# Microprocessor_and_CAN.net
KiCad netlist of a schematic drawn in Altium Designer
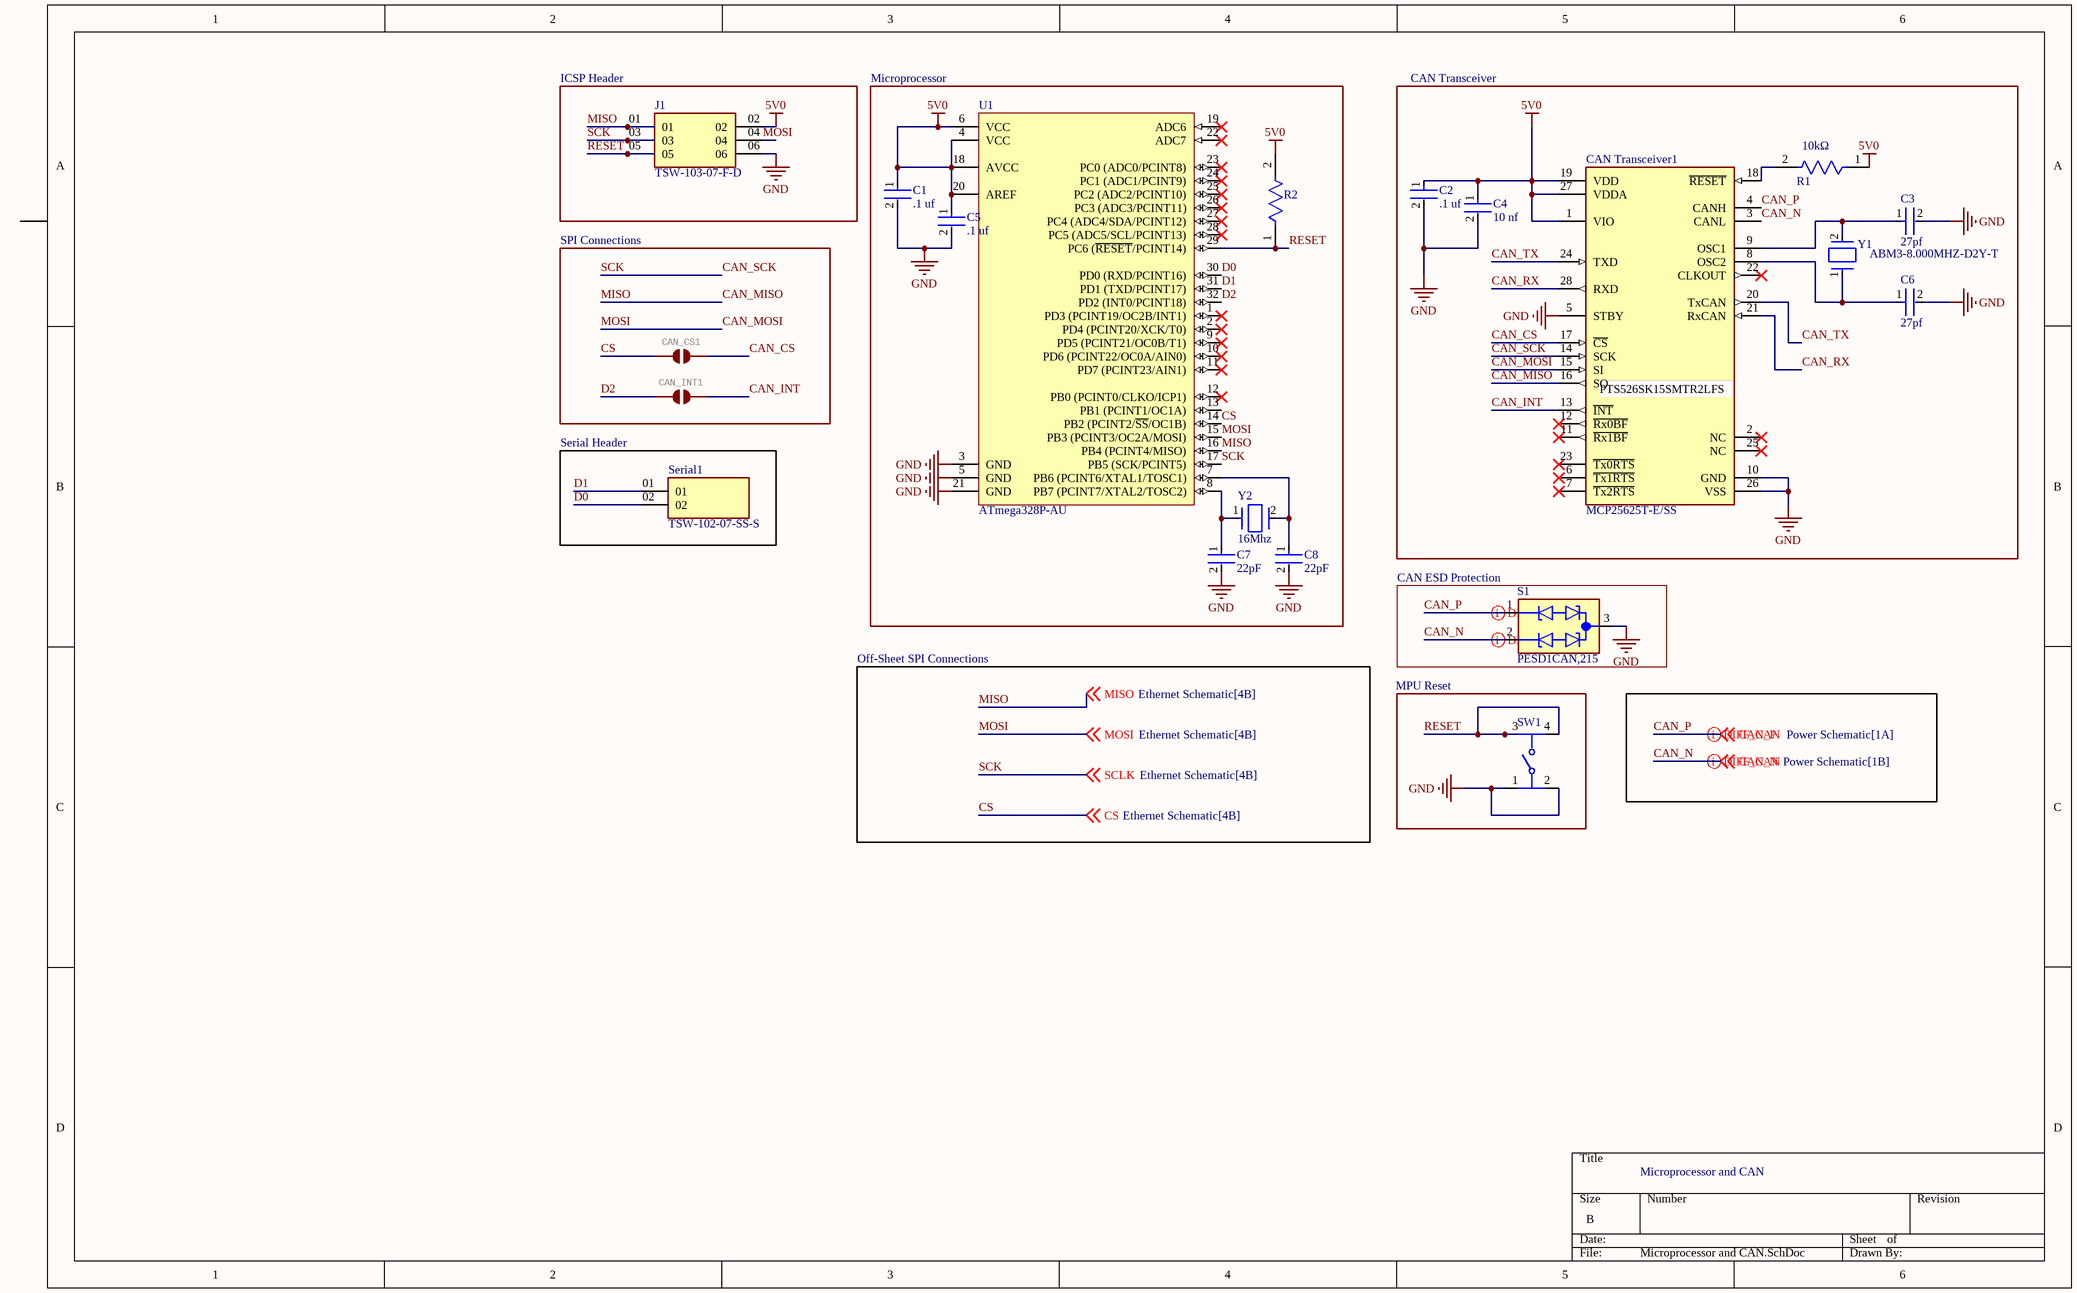
[diagram p0: Microprocessor and CAN.SchDoc]

(export (version "E")
  (design (tool "Eeschema 10.0.6"))
  (components
    (comp (ref "C1")
      (value ".1 uf")
      (footprint "FP-0805-L_2_01_0_2-W_1_25-IPC_B")
      (description "General Purpose Ceramic Capacitor, 0805, 100nF, 10%, X7R, 15%, 100V")
      (fields (field (name "VOLTAGE") "100V") (field (name "TOLERANCE") "10%"))
      (libsource (lib "Altium Content Vault") (part "b4654b650e69147ec39a6b967a45e02"))
    )
    (comp (ref "C2")
      (value ".1 uf")
      (footprint "FP-0805-L_2_01_0_2-W_1_25-IPC_B")
      (description "General Purpose Ceramic Capacitor, 0805, 100nF, 10%, X7R, 15%, 100V")
      (fields (field (name "VOLTAGE") "100V") (field (name "TOLERANCE") "10%"))
      (libsource (lib "Altium Content Vault") (part "b4654b650e69147ec39a6b967a45e02"))
    )
    (comp (ref "C3")
      (value "27pf")
      (footprint "FP-GRM21B-0_15-IPC_C")
      (description "Chip Multilayer Ceramic Capacitors for General Purpose, 0805, 10uF, X5R, 15%, 10%, 25V")
      (fields (field (name "VOLTAGE") "25V") (field (name "TOLERANCE") "10%"))
      (libsource (lib "Altium Content Vault") (part "b4654b650e69147ec39a6b967a45e02"))
    )
    (comp (ref "C4")
      (value "10 nf")
      (footprint "FP-C0805C-DN-MFG")
      (description "CAP CER 10000PF 200V X7R 0805")
      (fields
        (field (name "OCTOPART") "https://octopart.com/c0805c103k2ractu-kemet-9138347")
        (field (name "MANUFACTURER PART NUMBER") "C0805C103K2RACTU")
      )
      (libsource (lib "Altium Content Vault") (part "b4654b650e69147ec39a6b967a45e02"))
    )
    (comp (ref "C5")
      (value ".1 uf")
      (footprint "FP-0805-L_2_01_0_2-W_1_25-IPC_B")
      (description "General Purpose Ceramic Capacitor, 0805, 100nF, 10%, X7R, 15%, 100V")
      (fields (field (name "VOLTAGE") "100V") (field (name "TOLERANCE") "10%"))
      (libsource (lib "Altium Content Vault") (part "b4654b650e69147ec39a6b967a45e02"))
    )
    (comp (ref "C6")
      (value "27pf")
      (footprint "FP-GRM21B-0_15-IPC_C")
      (description "Chip Multilayer Ceramic Capacitors for General Purpose, 0805, 10uF, X5R, 15%, 10%, 25V")
      (fields (field (name "VOLTAGE") "25V") (field (name "TOLERANCE") "10%"))
      (libsource (lib "Altium Content Vault") (part "b4654b650e69147ec39a6b967a45e02"))
    )
    (comp (ref "C7")
      (value "22pF")
      (footprint "FP-C0805C-DN-MFG")
      (description "Capacitor; Ceramic; Cap; 22.0pF; Tol 5%; SMT; Vol-Rtg 50V; C0G; Tape and Reel")
      (fields
        (field (name "OCTOPART") "https://octopart.com/c0805c220j5gactu-kemet-145470")
        (field (name "MANUFACTURER") "KEMET")
      )
      (libsource (lib "Altium Content Vault") (part "b4654b650e69147ec39a6b967a45e02"))
    )
    (comp (ref "C8")
      (value "22pF")
      (footprint "FP-C0805C-DN-MFG")
      (description "Capacitor; Ceramic; Cap; 22.0pF; Tol 5%; SMT; Vol-Rtg 50V; C0G; Tape and Reel")
      (fields
        (field (name "OCTOPART") "https://octopart.com/c0805c220j5gactu-kemet-145470")
        (field (name "MANUFACTURER") "KEMET")
      )
      (libsource (lib "Altium Content Vault") (part "b4654b650e69147ec39a6b967a45e02"))
    )
    (comp (ref "CAN Transceiver1")
      (value "MCP25625T-E/SS")
      (footprint "FP-C04-073-IPC_B")
      (description "1/1 Transceiver CANbus 28-SSOP")
      (libsource (lib "Altium Content Vault") (part "1eb43db0d86e80dbea2ef2edec005e1"))
    )
    (comp (ref "CAN_CS1")
      (value "~")
      (footprint "SMT-JUMPER_2_NO_SILK")
      (libsource (lib "SparkFun-Jumpers") (part "JUMPER-SMT_2_NO_SILK"))
    )
    (comp (ref "CAN_INT1")
      (value "~")
      (footprint "SMT-JUMPER_2_NO_SILK")
      (libsource (lib "SparkFun-Jumpers") (part "JUMPER-SMT_2_NO_SILK"))
    )
    (comp (ref "J1")
      (value "TSW-103-07-F-D")
      (footprint "TSW-103-07-F-D:SAMTEC_TSW-103-07-F-D")
      (fields (field (name "MF") "{'manufacturer': u'Samtec'}"))
      (libsource (lib "*") (part "TSW-103-07-F-D"))
    )
    (comp (ref "R1")
      (value "10kΩ")
      (footprint "FP-CRCW0805-e3-IPC_A")
      (description "RES Thick Film, 10kΩ, 1%, 0.125W, 100ppm/°C, 0805")
      (fields (field (name "TOLERANCE") "1%"))
      (libsource (lib "Altium Content Vault") (part "1029c3af85768c4190bb7ad29bc67b5"))
    )
    (comp (ref "R2")
      (value "CRCW080510K0FKEA")
      (footprint "FP-CRCW0805-e3-IPC_A")
      (description "RES Thick Film, 10kΩ, 1%, 0.125W, 100ppm/°C, 0805")
      (fields (field (name "TOLERANCE") "1%"))
      (libsource (lib "Altium Content Vault") (part "1029c3af85768c4190bb7ad29bc67b5"))
    )
    (comp (ref "S1")
      (value "PESD1CAN,215")
      (footprint "PESD1CAN,215:DIO_PESD1CAN,215")
      (fields (field (name "MF") "{'manufacturer': u'Nexperia USA Inc.'}"))
      (libsource (lib "*") (part "PESD1CAN,215"))
    )
    (comp (ref "Serial1")
      (value "TSW-102-07-SS-S")
      (footprint "TSW-102-07-SS-S:SAMTEC_TSW-102-07-SS-S")
      (fields (field (name "MF") "{'manufacturer': u'Samtec'}"))
      (libsource (lib "*") (part "TSW-102-07-SS-S"))
    )
    (comp (ref "SW1")
      (value "PTS526SK15SMTR2LFS")
      (footprint "FP-PTS526SK15SMTR2LFS-MFG")
      (description "TACT 5.2 X 5.2, 1.5 MM H, 260GF,")
      (fields
        (field (name "MANUFACTURER") "C&K")
        (field (name "OCTOPART") "https://octopart.com/pts526+sk15+smtr2+lfs-c%26k+components-100617999")
      )
      (libsource (lib "Altium Content Vault") (part "b8895f3f4cefb76e1819d2863dba89b"))
    )
    (comp (ref "U1")
      (value "ATmega328P-AU")
      (footprint "32A_M")
      (libsource (lib "Altium Content Vault") (part "MC-8B-ATM48-SQ32"))
    )
    (comp (ref "Y1")
      (value "ABM3-8.000MHZ-D2Y-T")
      (footprint "FP-ABM3-MFG")
      (description "Crystal 8MHz ±20ppm 18pF SMD-2 5mm x 3.2mm")
      (fields (field (name "TOLERANCE") "20ppm"))
      (libsource (lib "Altium Content Vault") (part "c23a69dc6c9e2f18f2079038eb95dd1"))
    )
    (comp (ref "Y2")
      (value "16Mhz")
      (footprint "FP-ABM3-MFG")
      (description "Crystal 16MHz ±20ppm 18pF SMD-2 5mm x 3.2mm")
      (fields (field (name "TOLERANCE") "20ppm"))
      (libsource (lib "Altium Content Vault") (part "c23a69dc6c9e2f18f2079038eb95dd1"))
    )
  )
  (nets
    (net (code "1") (name "/CAN_CS") (class "Default")
      (node (ref "CAN Transceiver1") (pin "17") (pinfunction "~{CS}_17") (pintype "input"))
      (node (ref "CAN_CS1") (pin "2") (pinfunction "2_2") (pintype "passive"))
    )
    (net (code "2") (name "/CAN_INT") (class "Default")
      (node (ref "CAN Transceiver1") (pin "13") (pinfunction "~{INT}_13") (pintype "output"))
      (node (ref "CAN_INT1") (pin "2") (pinfunction "2_2") (pintype "passive"))
    )
    (net (code "3") (name "/CAN_RX") (class "Default")
      (node (ref "CAN Transceiver1") (pin "21") (pinfunction "RxCAN_21") (pintype "input"))
      (node (ref "CAN Transceiver1") (pin "28") (pinfunction "RXD_28") (pintype "output"))
    )
    (net (code "4") (name "/CAN_TX") (class "Default")
      (node (ref "CAN Transceiver1") (pin "20") (pinfunction "TxCAN_20") (pintype "output"))
      (node (ref "CAN Transceiver1") (pin "24") (pinfunction "TXD_24") (pintype "input"))
    )
    (net (code "5") (name "/D0") (class "Default")
      (node (ref "Serial1") (pin "02") (pinfunction "02_02") (pintype "passive"))
      (node (ref "U1") (pin "30") (pinfunction "PD0_(RXD/PCINT16)_30") (pintype "bidirectional"))
    )
    (net (code "6") (name "/D1") (class "Default")
      (node (ref "Serial1") (pin "01") (pinfunction "01_01") (pintype "passive"))
      (node (ref "U1") (pin "31") (pinfunction "PD1_(TXD/PCINT17)_31") (pintype "bidirectional"))
    )
    (net (code "7") (name "/D2") (class "Default")
      (node (ref "CAN_INT1") (pin "1") (pinfunction "1_1") (pintype "passive"))
      (node (ref "U1") (pin "32") (pinfunction "PD2_(INT0/PCINT18)_32") (pintype "bidirectional"))
    )
    (net (code "8") (name "/RESET") (class "Default")
      (node (ref "J1") (pin "05") (pinfunction "05_05") (pintype "passive"))
      (node (ref "R2") (pin "1") (pinfunction "1_1") (pintype "passive"))
      (node (ref "SW1") (pin "3") (pinfunction "3_3") (pintype "passive"))
      (node (ref "SW1") (pin "4") (pinfunction "4_4") (pintype "passive"))
      (node (ref "U1") (pin "29") (pinfunction "PC6_(~{RESET}/PCINT14)_29") (pintype "bidirectional"))
    )
    (net (code "9") (name "5V0") (class "Default")
      (node (ref "C1") (pin "1") (pinfunction "1_1") (pintype "passive"))
      (node (ref "C2") (pin "1") (pinfunction "1_1") (pintype "passive"))
      (node (ref "C4") (pin "1") (pinfunction "1_1") (pintype "passive"))
      (node (ref "C5") (pin "1") (pinfunction "1_1") (pintype "passive"))
      (node (ref "CAN Transceiver1") (pin "1") (pinfunction "VIO_1") (pintype "power_in"))
      (node (ref "CAN Transceiver1") (pin "19") (pinfunction "VDD_19") (pintype "power_in"))
      (node (ref "CAN Transceiver1") (pin "27") (pinfunction "VDDA_27") (pintype "power_in"))
      (node (ref "J1") (pin "02") (pinfunction "02_02") (pintype "passive"))
      (node (ref "R1") (pin "1") (pinfunction "1_1") (pintype "passive"))
      (node (ref "R2") (pin "2") (pinfunction "2_2") (pintype "passive"))
      (node (ref "U1") (pin "18") (pinfunction "AVCC_18") (pintype "power_in"))
      (node (ref "U1") (pin "20") (pinfunction "AREF_20") (pintype "passive"))
      (node (ref "U1") (pin "4") (pinfunction "VCC_4") (pintype "power_in"))
      (node (ref "U1") (pin "6") (pinfunction "VCC_6") (pintype "power_in"))
    )
    (net (code "10") (name "CAN_N") (class "Default")
      (node (ref "CAN Transceiver1") (pin "3") (pinfunction "CANL_3") (pintype "passive"))
      (node (ref "S1") (pin "2") (pinfunction "C2_2") (pintype "passive"))
    )
    (net (code "11") (name "CAN_P") (class "Default")
      (node (ref "CAN Transceiver1") (pin "4") (pinfunction "CANH_4") (pintype "passive"))
      (node (ref "S1") (pin "1") (pinfunction "C1_1") (pintype "passive"))
    )
    (net (code "12") (name "CS") (class "Default")
      (node (ref "CAN_CS1") (pin "1") (pinfunction "1_1") (pintype "passive"))
      (node (ref "U1") (pin "14") (pinfunction "PB2_(PCINT2/~{SS}/OC1B)_14") (pintype "bidirectional"))
    )
    (net (code "13") (name "GND") (class "Default")
      (node (ref "C1") (pin "2") (pinfunction "2_2") (pintype "passive"))
      (node (ref "C2") (pin "2") (pinfunction "2_2") (pintype "passive"))
      (node (ref "C3") (pin "2") (pinfunction "2_2") (pintype "passive"))
      (node (ref "C4") (pin "2") (pinfunction "2_2") (pintype "passive"))
      (node (ref "C5") (pin "2") (pinfunction "2_2") (pintype "passive"))
      (node (ref "C6") (pin "2") (pinfunction "2_2") (pintype "passive"))
      (node (ref "C7") (pin "2") (pinfunction "2_2") (pintype "passive"))
      (node (ref "C8") (pin "2") (pinfunction "2_2") (pintype "passive"))
      (node (ref "CAN Transceiver1") (pin "10") (pinfunction "GND_10") (pintype "power_in"))
      (node (ref "CAN Transceiver1") (pin "26") (pinfunction "VSS_26") (pintype "power_in"))
      (node (ref "CAN Transceiver1") (pin "5") (pinfunction "STBY_5") (pintype "passive"))
      (node (ref "J1") (pin "06") (pinfunction "06_06") (pintype "passive"))
      (node (ref "S1") (pin "3") (pinfunction "CC_3") (pintype "passive"))
      (node (ref "SW1") (pin "1") (pinfunction "1_1") (pintype "passive"))
      (node (ref "SW1") (pin "2") (pinfunction "2_2") (pintype "passive"))
      (node (ref "U1") (pin "21") (pinfunction "GND_21") (pintype "power_in"))
      (node (ref "U1") (pin "3") (pinfunction "GND_3") (pintype "power_in"))
      (node (ref "U1") (pin "5") (pinfunction "GND_5") (pintype "power_in"))
    )
    (net (code "14") (name "MISO") (class "Default")
      (node (ref "CAN Transceiver1") (pin "16") (pinfunction "SO_16") (pintype "output"))
      (node (ref "J1") (pin "01") (pinfunction "01_01") (pintype "passive"))
      (node (ref "U1") (pin "16") (pinfunction "PB4_(PCINT4/MISO)_16") (pintype "bidirectional"))
    )
    (net (code "15") (name "MOSI") (class "Default")
      (node (ref "CAN Transceiver1") (pin "15") (pinfunction "SI_15") (pintype "input"))
      (node (ref "J1") (pin "04") (pinfunction "04_04") (pintype "passive"))
      (node (ref "U1") (pin "15") (pinfunction "PB3_(PCINT3/OC2A/MOSI)_15") (pintype "bidirectional"))
    )
    (net (code "16") (name "Net-(CAN Transceiver1-OSC1)") (class "Default")
      (node (ref "C3") (pin "1") (pinfunction "1_1") (pintype "passive"))
      (node (ref "CAN Transceiver1") (pin "9") (pinfunction "OSC1_9") (pintype "passive"))
      (node (ref "Y1") (pin "2") (pinfunction "2_2") (pintype "passive"))
    )
    (net (code "17") (name "Net-(CAN Transceiver1-OSC2)") (class "Default")
      (node (ref "C6") (pin "1") (pinfunction "1_1") (pintype "passive"))
      (node (ref "CAN Transceiver1") (pin "8") (pinfunction "OSC2_8") (pintype "passive"))
      (node (ref "Y1") (pin "1") (pinfunction "1_1") (pintype "passive"))
    )
    (net (code "18") (name "Net-(CAN Transceiver1-~{RESET})") (class "Default")
      (node (ref "CAN Transceiver1") (pin "18") (pinfunction "~{RESET}_18") (pintype "input"))
      (node (ref "R1") (pin "2") (pinfunction "2_2") (pintype "passive"))
    )
    (net (code "19") (name "Net-(U1-PB6_(PCINT6{slash}XTAL1{slash}TOSC1))") (class "Default")
      (node (ref "C8") (pin "1") (pinfunction "1_1") (pintype "passive"))
      (node (ref "U1") (pin "7") (pinfunction "PB6_(PCINT6/XTAL1/TOSC1)_7") (pintype "bidirectional"))
      (node (ref "Y2") (pin "2") (pinfunction "2_2") (pintype "passive"))
    )
    (net (code "20") (name "Net-(U1-PB7_(PCINT7{slash}XTAL2{slash}TOSC2))") (class "Default")
      (node (ref "C7") (pin "1") (pinfunction "1_1") (pintype "passive"))
      (node (ref "U1") (pin "8") (pinfunction "PB7_(PCINT7/XTAL2/TOSC2)_8") (pintype "bidirectional"))
      (node (ref "Y2") (pin "1") (pinfunction "1_1") (pintype "passive"))
    )
    (net (code "21") (name "SCLK") (class "Default")
      (node (ref "CAN Transceiver1") (pin "14") (pinfunction "SCK_14") (pintype "input"))
      (node (ref "J1") (pin "03") (pinfunction "03_03") (pintype "passive"))
      (node (ref "U1") (pin "17") (pinfunction "PB5_(SCK/PCINT5)_17") (pintype "bidirectional"))
    )
    (net (code "22") (name "unconnected-(CAN Transceiver1-CLKOUT-Pad22)") (class "Default")
      (node (ref "CAN Transceiver1") (pin "22") (pinfunction "CLKOUT_22") (pintype "output+no_connect"))
    )
    (net (code "23") (name "unconnected-(CAN Transceiver1-NC-Pad2)") (class "Default")
      (node (ref "CAN Transceiver1") (pin "2") (pinfunction "NC_2") (pintype "passive+no_connect"))
    )
    (net (code "24") (name "unconnected-(CAN Transceiver1-NC-Pad25)") (class "Default")
      (node (ref "CAN Transceiver1") (pin "25") (pinfunction "NC_25") (pintype "passive+no_connect"))
    )
    (net (code "25") (name "unconnected-(CAN Transceiver1-~{Rx0BF}-Pad12)") (class "Default")
      (node (ref "CAN Transceiver1") (pin "12") (pinfunction "~{Rx0BF}_12") (pintype "output+no_connect"))
    )
    (net (code "26") (name "unconnected-(CAN Transceiver1-~{Rx1BF}-Pad11)") (class "Default")
      (node (ref "CAN Transceiver1") (pin "11") (pinfunction "~{Rx1BF}_11") (pintype "output+no_connect"))
    )
    (net (code "27") (name "unconnected-(CAN Transceiver1-~{Tx0RTS}-Pad23)") (class "Default")
      (node (ref "CAN Transceiver1") (pin "23") (pinfunction "~{Tx0RTS}_23") (pintype "passive+no_connect"))
    )
    (net (code "28") (name "unconnected-(CAN Transceiver1-~{Tx1RTS}-Pad6)") (class "Default")
      (node (ref "CAN Transceiver1") (pin "6") (pinfunction "~{Tx1RTS}_6") (pintype "passive+no_connect"))
    )
    (net (code "29") (name "unconnected-(CAN Transceiver1-~{Tx2RTS}-Pad7)") (class "Default")
      (node (ref "CAN Transceiver1") (pin "7") (pinfunction "~{Tx2RTS}_7") (pintype "passive+no_connect"))
    )
    (net (code "30") (name "unconnected-(U1-ADC6-Pad19)") (class "Default")
      (node (ref "U1") (pin "19") (pinfunction "ADC6_19") (pintype "input+no_connect"))
    )
    (net (code "31") (name "unconnected-(U1-ADC7-Pad22)") (class "Default")
      (node (ref "U1") (pin "22") (pinfunction "ADC7_22") (pintype "input+no_connect"))
    )
    (net (code "32") (name "unconnected-(U1-PB0_(PCINT0{slash}CLKO{slash}ICP1)-Pad12)") (class "Default")
      (node (ref "U1") (pin "12") (pinfunction "PB0_(PCINT0/CLKO/ICP1)_12") (pintype "bidirectional+no_connect"))
    )
    (net (code "33") (name "unconnected-(U1-PB1_(PCINT1{slash}OC1A)-Pad13)") (class "Default")
      (node (ref "U1") (pin "13") (pinfunction "PB1_(PCINT1/OC1A)_13") (pintype "bidirectional"))
    )
    (net (code "34") (name "unconnected-(U1-PC0_(ADC0{slash}PCINT8)-Pad23)") (class "Default")
      (node (ref "U1") (pin "23") (pinfunction "PC0_(ADC0/PCINT8)_23") (pintype "bidirectional+no_connect"))
    )
    (net (code "35") (name "unconnected-(U1-PC1_(ADC1{slash}PCINT9)-Pad24)") (class "Default")
      (node (ref "U1") (pin "24") (pinfunction "PC1_(ADC1/PCINT9)_24") (pintype "bidirectional+no_connect"))
    )
    (net (code "36") (name "unconnected-(U1-PC2_(ADC2{slash}PCINT10)-Pad25)") (class "Default")
      (node (ref "U1") (pin "25") (pinfunction "PC2_(ADC2/PCINT10)_25") (pintype "bidirectional+no_connect"))
    )
    (net (code "37") (name "unconnected-(U1-PC3_(ADC3{slash}PCINT11)-Pad26)") (class "Default")
      (node (ref "U1") (pin "26") (pinfunction "PC3_(ADC3/PCINT11)_26") (pintype "bidirectional+no_connect"))
    )
    (net (code "38") (name "unconnected-(U1-PC4_(ADC4{slash}SDA{slash}PCINT12)-Pad27)") (class "Default")
      (node (ref "U1") (pin "27") (pinfunction "PC4_(ADC4/SDA/PCINT12)_27") (pintype "bidirectional+no_connect"))
    )
    (net (code "39") (name "unconnected-(U1-PC5_(ADC5{slash}SCL{slash}PCINT13)-Pad28)") (class "Default")
      (node (ref "U1") (pin "28") (pinfunction "PC5_(ADC5/SCL/PCINT13)_28") (pintype "bidirectional+no_connect"))
    )
    (net (code "40") (name "unconnected-(U1-PD3_(PCINT19{slash}OC2B{slash}INT1)-Pad1)") (class "Default")
      (node (ref "U1") (pin "1") (pinfunction "PD3_(PCINT19/OC2B/INT1)_1") (pintype "bidirectional+no_connect"))
    )
    (net (code "41") (name "unconnected-(U1-PD4_(PCINT20{slash}XCK{slash}T0)-Pad2)") (class "Default")
      (node (ref "U1") (pin "2") (pinfunction "PD4_(PCINT20/XCK/T0)_2") (pintype "bidirectional+no_connect"))
    )
    (net (code "42") (name "unconnected-(U1-PD5_(PCINT21{slash}OC0B{slash}T1)-Pad9)") (class "Default")
      (node (ref "U1") (pin "9") (pinfunction "PD5_(PCINT21/OC0B/T1)_9") (pintype "bidirectional+no_connect"))
    )
    (net (code "43") (name "unconnected-(U1-PD6_(PCINT22{slash}OC0A{slash}AIN0)-Pad10)") (class "Default")
      (node (ref "U1") (pin "10") (pinfunction "PD6_(PCINT22/OC0A/AIN0)_10") (pintype "bidirectional+no_connect"))
    )
    (net (code "44") (name "unconnected-(U1-PD7_(PCINT23{slash}AIN1)-Pad11)") (class "Default")
      (node (ref "U1") (pin "11") (pinfunction "PD7_(PCINT23/AIN1)_11") (pintype "bidirectional+no_connect"))
    )
  )
)
